# Piezo.net
KiCad netlist of a schematic drawn in EAGLE
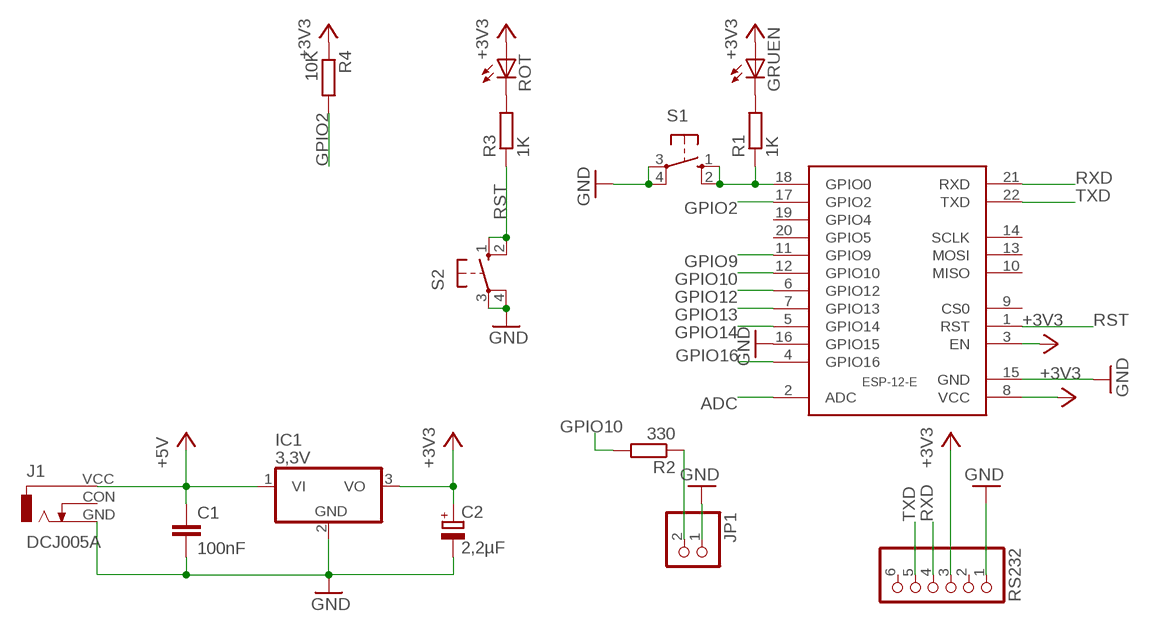
[diagram p0: schematic, sheet 1]

(export (version "E")
  (design (tool "Eeschema 10.0.6"))
  (components
    (comp (ref "C1")
      (value "100nF")
      (footprint "eagle-import:C050-030X075")
      (libsource (lib "eagle-import") (part "C-EU050-030X075"))
    )
    (comp (ref "C2")
      (value "2,2µF")
      (footprint "eagle-import:E2,5-6")
      (libsource (lib "eagle-import") (part "CPOL-EUE2.5-6"))
    )
    (comp (ref "GRUEN")
      (value "LED5MM")
      (footprint "eagle-import:LED5MM")
      (libsource (lib "eagle-import") (part "LED5MM"))
    )
    (comp (ref "IC1")
      (value "3,3V")
      (footprint "eagle-import:TO220V")
      (libsource (lib "eagle-import") (part "78TV05"))
    )
    (comp (ref "J1")
      (value "DCJ005A")
      (footprint "eagle-import:DC005A")
      (libsource (lib "eagle-import") (part "DCJ005A"))
    )
    (comp (ref "JP1")
      (value "PINHD-1X2")
      (footprint "eagle-import:1X02")
      (libsource (lib "eagle-import") (part "PINHD-1X2"))
    )
    (comp (ref "R1")
      (value "1K")
      (footprint "eagle-import:0207_10")
      (libsource (lib "eagle-import") (part "R-EU_0207/10"))
    )
    (comp (ref "R2")
      (value "330")
      (footprint "eagle-import:0207_10")
      (libsource (lib "eagle-import") (part "R-EU_0207/10"))
    )
    (comp (ref "R3")
      (value "1K")
      (footprint "eagle-import:0207_10")
      (libsource (lib "eagle-import") (part "R-EU_0207/10"))
    )
    (comp (ref "R4")
      (value "10K")
      (footprint "eagle-import:0207_10")
      (libsource (lib "eagle-import") (part "R-EU_0207/10"))
    )
    (comp (ref "ROT")
      (value "LED5MM")
      (footprint "eagle-import:LED5MM")
      (libsource (lib "eagle-import") (part "LED5MM"))
    )
    (comp (ref "RS232")
      (value "PINHD-1X6")
      (footprint "eagle-import:1X06")
      (libsource (lib "eagle-import") (part "PINHD-1X6"))
    )
    (comp (ref "S1")
      (value "10-XX")
      (footprint "eagle-import:B3F-10XX")
      (fields (field (name "MPN") "B3F-1000"))
      (libsource (lib "eagle-import") (part "10-XX"))
    )
    (comp (ref "S2")
      (value "10-XX")
      (footprint "eagle-import:B3F-10XX")
      (fields (field (name "MPN") "B3F-1000"))
      (libsource (lib "eagle-import") (part "10-XX"))
    )
    (comp (ref "U$1")
      (value "ESP-12-E")
      (footprint "eagle-import:ESP-12-E")
      (libsource (lib "eagle-import") (part "ESP-12-E"))
    )
  )
  (nets
    (net (code "1") (name "+3V3") (class "Default")
      (node (ref "C2") (pin "+") (pinfunction "+_+") (pintype "passive"))
      (node (ref "GRUEN") (pin "A") (pinfunction "A_A") (pintype "passive"))
      (node (ref "IC1") (pin "3") (pinfunction "VO_3") (pintype "passive"))
      (node (ref "R4") (pin "1") (pinfunction "1_1") (pintype "passive"))
      (node (ref "ROT") (pin "A") (pinfunction "A_A") (pintype "passive"))
      (node (ref "RS232") (pin "3") (pinfunction "3_3") (pintype "passive"))
      (node (ref "U$1") (pin "3") (pinfunction "EN_3") (pintype "bidirectional"))
      (node (ref "U$1") (pin "8") (pinfunction "VCC_8") (pintype "power_in"))
    )
    (net (code "2") (name "+5V") (class "Default")
      (node (ref "C1") (pin "1") (pinfunction "1_1") (pintype "passive"))
      (node (ref "IC1") (pin "1") (pinfunction "VI_1") (pintype "input"))
      (node (ref "J1") (pin "VCC") (pinfunction "1_VCC") (pintype "passive"))
    )
    (net (code "3") (name "/ADC") (class "Default")
      (node (ref "U$1") (pin "2") (pinfunction "ADC_2") (pintype "bidirectional"))
    )
    (net (code "4") (name "/GPIO2") (class "Default")
      (node (ref "R4") (pin "2") (pinfunction "2_2") (pintype "passive"))
      (node (ref "U$1") (pin "17") (pinfunction "GPIO2_17") (pintype "bidirectional"))
    )
    (net (code "5") (name "/GPIO9") (class "Default")
      (node (ref "U$1") (pin "11") (pinfunction "GPIO9_11") (pintype "bidirectional"))
    )
    (net (code "6") (name "/GPIO10") (class "Default")
      (node (ref "R2") (pin "2") (pinfunction "2_2") (pintype "passive"))
      (node (ref "U$1") (pin "12") (pinfunction "GPIO10_12") (pintype "bidirectional"))
    )
    (net (code "7") (name "/GPIO12") (class "Default")
      (node (ref "U$1") (pin "6") (pinfunction "GPIO12_6") (pintype "bidirectional"))
    )
    (net (code "8") (name "/GPIO13") (class "Default")
      (node (ref "U$1") (pin "7") (pinfunction "GPIO13_7") (pintype "bidirectional"))
    )
    (net (code "9") (name "/GPIO14") (class "Default")
      (node (ref "U$1") (pin "5") (pinfunction "GPIO14_5") (pintype "bidirectional"))
    )
    (net (code "10") (name "/GPIO16") (class "Default")
      (node (ref "U$1") (pin "4") (pinfunction "GPIO16_4") (pintype "bidirectional"))
    )
    (net (code "11") (name "/RST") (class "Default")
      (node (ref "R3") (pin "1") (pinfunction "1_1") (pintype "passive"))
      (node (ref "S2") (pin "1") (pinfunction "S_1") (pintype "passive"))
      (node (ref "S2") (pin "2") (pinfunction "S1_2") (pintype "passive"))
      (node (ref "U$1") (pin "1") (pinfunction "RST_1") (pintype "bidirectional"))
    )
    (net (code "12") (name "/RXD") (class "Default")
      (node (ref "RS232") (pin "4") (pinfunction "4_4") (pintype "passive"))
      (node (ref "U$1") (pin "21") (pinfunction "RXD_21") (pintype "bidirectional"))
    )
    (net (code "13") (name "/TXD") (class "Default")
      (node (ref "RS232") (pin "5") (pinfunction "5_5") (pintype "passive"))
      (node (ref "U$1") (pin "22") (pinfunction "TXD_22") (pintype "bidirectional"))
    )
    (net (code "14") (name "GND") (class "Default")
      (node (ref "C1") (pin "2") (pinfunction "2_2") (pintype "passive"))
      (node (ref "C2") (pin "-") (pinfunction "-_-") (pintype "passive"))
      (node (ref "IC1") (pin "2") (pinfunction "GND_2") (pintype "passive"))
      (node (ref "J1") (pin "GND") (pinfunction "3_GND") (pintype "passive"))
      (node (ref "JP1") (pin "1") (pinfunction "1_1") (pintype "passive"))
      (node (ref "RS232") (pin "1") (pinfunction "1_1") (pintype "passive"))
      (node (ref "S1") (pin "3") (pinfunction "P_3") (pintype "passive"))
      (node (ref "S1") (pin "4") (pinfunction "P1_4") (pintype "passive"))
      (node (ref "S2") (pin "3") (pinfunction "P_3") (pintype "passive"))
      (node (ref "S2") (pin "4") (pinfunction "P1_4") (pintype "passive"))
      (node (ref "U$1") (pin "15") (pinfunction "GND_15") (pintype "power_in"))
      (node (ref "U$1") (pin "16") (pinfunction "GPIO15_16") (pintype "bidirectional"))
    )
    (net (code "15") (name "Net-(GRUEN-C)") (class "Default")
      (node (ref "GRUEN") (pin "K") (pinfunction "C_K") (pintype "passive"))
      (node (ref "R1") (pin "2") (pinfunction "2_2") (pintype "passive"))
    )
    (net (code "16") (name "Net-(JP1-Pad2)") (class "Default")
      (node (ref "JP1") (pin "2") (pinfunction "2_2") (pintype "passive"))
      (node (ref "R2") (pin "1") (pinfunction "1_1") (pintype "passive"))
    )
    (net (code "17") (name "Net-(ROT-C)") (class "Default")
      (node (ref "R3") (pin "2") (pinfunction "2_2") (pintype "passive"))
      (node (ref "ROT") (pin "K") (pinfunction "C_K") (pintype "passive"))
    )
    (net (code "18") (name "Net-(S1-S)") (class "Default")
      (node (ref "R1") (pin "1") (pinfunction "1_1") (pintype "passive"))
      (node (ref "S1") (pin "1") (pinfunction "S_1") (pintype "passive"))
      (node (ref "S1") (pin "2") (pinfunction "S1_2") (pintype "passive"))
      (node (ref "U$1") (pin "18") (pinfunction "GPIO0_18") (pintype "bidirectional"))
    )
    (net (code "19") (name "unconnected-(J1-2-PadCON)") (class "Default")
      (node (ref "J1") (pin "CON") (pinfunction "2_CON") (pintype "passive"))
    )
    (net (code "20") (name "unconnected-(RS232-Pad2)") (class "Default")
      (node (ref "RS232") (pin "2") (pinfunction "2_2") (pintype "passive"))
    )
    (net (code "21") (name "unconnected-(RS232-Pad6)") (class "Default")
      (node (ref "RS232") (pin "6") (pinfunction "6_6") (pintype "passive"))
    )
    (net (code "22") (name "unconnected-(U$1-CS0-Pad9)") (class "Default")
      (node (ref "U$1") (pin "9") (pinfunction "CS0_9") (pintype "bidirectional"))
    )
    (net (code "23") (name "unconnected-(U$1-GPIO4-Pad19)") (class "Default")
      (node (ref "U$1") (pin "19") (pinfunction "GPIO4_19") (pintype "bidirectional"))
    )
    (net (code "24") (name "unconnected-(U$1-GPIO5-Pad20)") (class "Default")
      (node (ref "U$1") (pin "20") (pinfunction "GPIO5_20") (pintype "bidirectional"))
    )
    (net (code "25") (name "unconnected-(U$1-MISO-Pad10)") (class "Default")
      (node (ref "U$1") (pin "10") (pinfunction "MISO_10") (pintype "bidirectional"))
    )
    (net (code "26") (name "unconnected-(U$1-MOSI-Pad13)") (class "Default")
      (node (ref "U$1") (pin "13") (pinfunction "MOSI_13") (pintype "bidirectional"))
    )
    (net (code "27") (name "unconnected-(U$1-SCLK-Pad14)") (class "Default")
      (node (ref "U$1") (pin "14") (pinfunction "SCLK_14") (pintype "bidirectional"))
    )
  )
)
